# Schematics-1.net
KiCad netlist of a schematic drawn in EAGLE
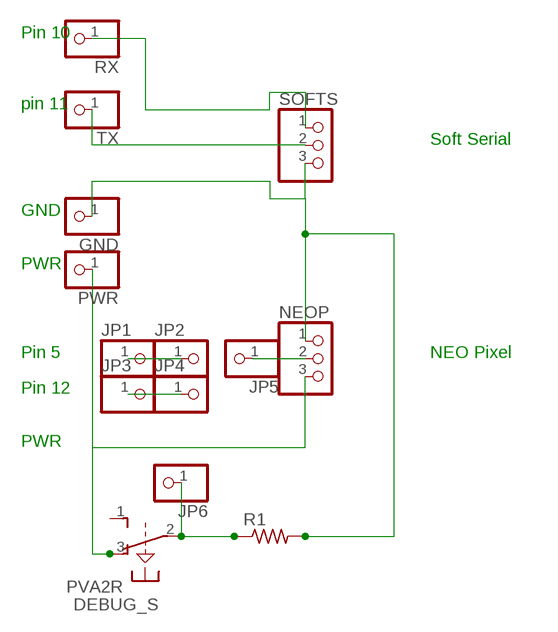
[diagram p0: schematic, sheet 1]

(export (version "E")
  (design (tool "Eeschema 10.0.6"))
  (components
    (comp (ref "DEBUG_S")
      (value "PVA2R")
      (footprint "eagle-import:PVA2R")
      (libsource (lib "eagle-import") (part "PVA2R"))
    )
    (comp (ref "GND")
      (value "PINHD-1X1CB")
      (footprint "eagle-import:1X01-CLEANBIG")
      (libsource (lib "eagle-import") (part "PINHD-1X1CB"))
    )
    (comp (ref "JP1")
      (value "PINHD-1X1CB")
      (footprint "eagle-import:1X01-CLEANBIG")
      (libsource (lib "eagle-import") (part "PINHD-1X1CB"))
    )
    (comp (ref "JP2")
      (value "PINHD-1X1CB")
      (footprint "eagle-import:1X01-CLEANBIG")
      (libsource (lib "eagle-import") (part "PINHD-1X1CB"))
    )
    (comp (ref "JP3")
      (value "PINHD-1X1CB")
      (footprint "eagle-import:1X01-CLEANBIG")
      (libsource (lib "eagle-import") (part "PINHD-1X1CB"))
    )
    (comp (ref "JP4")
      (value "PINHD-1X1CB")
      (footprint "eagle-import:1X01-CLEANBIG")
      (libsource (lib "eagle-import") (part "PINHD-1X1CB"))
    )
    (comp (ref "JP5")
      (value "PINHD-1X1CB")
      (footprint "eagle-import:1X01-CLEANBIG")
      (libsource (lib "eagle-import") (part "PINHD-1X1CB"))
    )
    (comp (ref "JP6")
      (value "PINHD-1X1CB")
      (footprint "eagle-import:1X01-CLEANBIG")
      (libsource (lib "eagle-import") (part "PINHD-1X1CB"))
    )
    (comp (ref "NEOP")
      (value "PINHD-1X3CB")
      (footprint "eagle-import:1X03-CLEANBIG")
      (libsource (lib "eagle-import") (part "PINHD-1X3CB"))
    )
    (comp (ref "PWR")
      (value "PINHD-1X1CB")
      (footprint "eagle-import:1X01-CLEANBIG")
      (libsource (lib "eagle-import") (part "PINHD-1X1CB"))
    )
    (comp (ref "R1")
      (value "R-US_0204/7")
      (footprint "eagle-import:0204_7")
      (libsource (lib "eagle-import") (part "R-US_0204/7"))
    )
    (comp (ref "RX")
      (value "PINHD-1X1CB")
      (footprint "eagle-import:1X01-CLEANBIG")
      (libsource (lib "eagle-import") (part "PINHD-1X1CB"))
    )
    (comp (ref "SOFTS")
      (value "PINHD-1X3CB")
      (footprint "eagle-import:1X03-CLEANBIG")
      (libsource (lib "eagle-import") (part "PINHD-1X3CB"))
    )
    (comp (ref "TX")
      (value "PINHD-1X1CB")
      (footprint "eagle-import:1X01-CLEANBIG")
      (libsource (lib "eagle-import") (part "PINHD-1X1CB"))
    )
  )
  (nets
    (net (code "1") (name "Net-(DEBUG_SA-O)") (class "Default")
      (node (ref "DEBUG_S") (pin "3") (pinfunction "O_3") (pintype "passive"))
      (node (ref "NEOP") (pin "3") (pinfunction "3_3") (pintype "passive"))
      (node (ref "PWR") (pin "1") (pinfunction "1_1") (pintype "passive"))
    )
    (net (code "2") (name "Net-(DEBUG_SA-P)") (class "Default")
      (node (ref "DEBUG_S") (pin "2") (pinfunction "P_2") (pintype "passive"))
      (node (ref "JP6") (pin "1") (pinfunction "1_1") (pintype "passive"))
      (node (ref "R1") (pin "1") (pinfunction "1_1") (pintype "passive"))
    )
    (net (code "3") (name "Net-(GND-Pad1)") (class "Default")
      (node (ref "GND") (pin "1") (pinfunction "1_1") (pintype "passive"))
      (node (ref "NEOP") (pin "1") (pinfunction "1_1") (pintype "passive"))
      (node (ref "R1") (pin "2") (pinfunction "2_2") (pintype "passive"))
      (node (ref "SOFTS") (pin "3") (pinfunction "3_3") (pintype "passive"))
    )
    (net (code "4") (name "Net-(JP1-Pad1)") (class "Default")
      (node (ref "JP1") (pin "1") (pinfunction "1_1") (pintype "passive"))
      (node (ref "JP2") (pin "1") (pinfunction "1_1") (pintype "passive"))
    )
    (net (code "5") (name "Net-(JP3-Pad1)") (class "Default")
      (node (ref "JP3") (pin "1") (pinfunction "1_1") (pintype "passive"))
      (node (ref "JP4") (pin "1") (pinfunction "1_1") (pintype "passive"))
    )
    (net (code "6") (name "Net-(JP5-Pad1)") (class "Default")
      (node (ref "JP5") (pin "1") (pinfunction "1_1") (pintype "passive"))
      (node (ref "NEOP") (pin "2") (pinfunction "2_2") (pintype "passive"))
    )
    (net (code "7") (name "Net-(RX-Pad1)") (class "Default")
      (node (ref "RX") (pin "1") (pinfunction "1_1") (pintype "passive"))
      (node (ref "SOFTS") (pin "1") (pinfunction "1_1") (pintype "passive"))
    )
    (net (code "8") (name "Net-(SOFTS-Pad2)") (class "Default")
      (node (ref "SOFTS") (pin "2") (pinfunction "2_2") (pintype "passive"))
      (node (ref "TX") (pin "1") (pinfunction "1_1") (pintype "passive"))
    )
    (net (code "9") (name "unconnected-(DEBUG_SA-S-Pad1)") (class "Default")
      (node (ref "DEBUG_S") (pin "1") (pinfunction "S_1") (pintype "passive"))
    )
  )
)
